# Connectors.net
KiCad netlist of a schematic drawn in Altium Designer
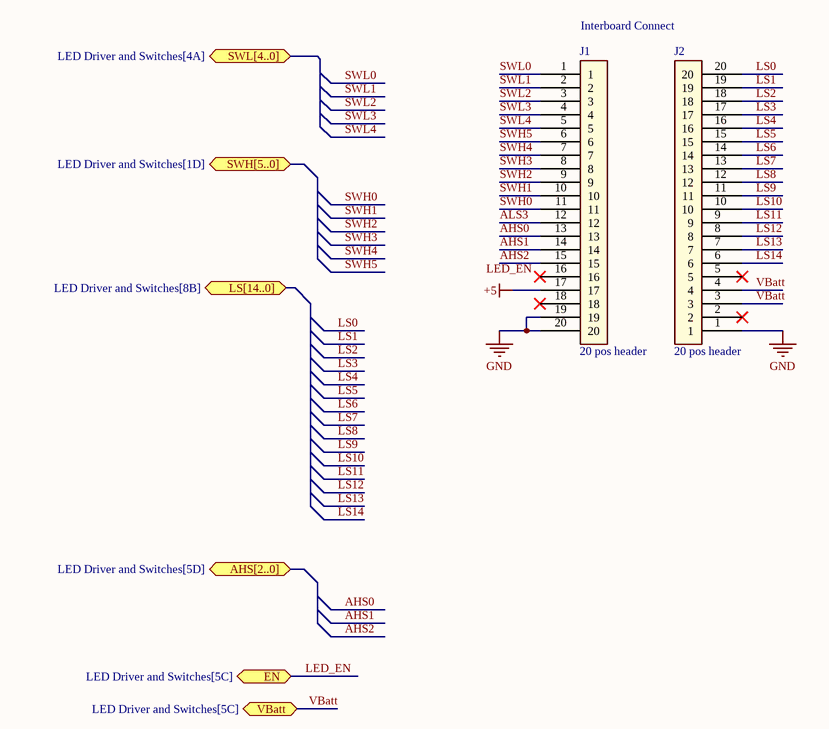
[diagram p0: Connectors.SchDoc]

(export (version "E")
  (design (tool "Eeschema 10.0.6"))
  (components
    (comp (ref "J1")
      (value "20 pos header")
      (footprint "20 pos header")
      (libsource (lib "2020-09-26_17-27-19") (part "20 pos header"))
    )
    (comp (ref "J2")
      (value "20 pos header")
      (footprint "20 pos header")
      (libsource (lib "") (part "20 pos header_1"))
    )
  )
  (nets
    (net (code "1") (name "+5") (class "Default")
      (node (ref "J1") (pin "17") (pinfunction "17_17") (pintype "passive"))
    )
    (net (code "2") (name "/AHS0") (class "Default")
      (node (ref "J1") (pin "13") (pinfunction "13_13") (pintype "passive"))
    )
    (net (code "3") (name "/AHS1") (class "Default")
      (node (ref "J1") (pin "14") (pinfunction "14_14") (pintype "passive"))
    )
    (net (code "4") (name "/AHS2") (class "Default")
      (node (ref "J1") (pin "15") (pinfunction "15_15") (pintype "passive"))
    )
    (net (code "6") (name "/ALS3") (class "Default")
      (node (ref "J1") (pin "12") (pinfunction "12_12") (pintype "passive"))
    )
    (net (code "8") (name "/LS0") (class "Default")
      (node (ref "J2") (pin "20") (pinfunction "20_20") (pintype "passive"))
    )
    (net (code "9") (name "/LS1") (class "Default")
      (node (ref "J2") (pin "19") (pinfunction "19_19") (pintype "passive"))
    )
    (net (code "10") (name "/LS2") (class "Default")
      (node (ref "J2") (pin "18") (pinfunction "18_18") (pintype "passive"))
    )
    (net (code "11") (name "/LS3") (class "Default")
      (node (ref "J2") (pin "17") (pinfunction "17_17") (pintype "passive"))
    )
    (net (code "12") (name "/LS4") (class "Default")
      (node (ref "J2") (pin "16") (pinfunction "16_16") (pintype "passive"))
    )
    (net (code "13") (name "/LS5") (class "Default")
      (node (ref "J2") (pin "15") (pinfunction "15_15") (pintype "passive"))
    )
    (net (code "14") (name "/LS6") (class "Default")
      (node (ref "J2") (pin "14") (pinfunction "14_14") (pintype "passive"))
    )
    (net (code "15") (name "/LS7") (class "Default")
      (node (ref "J2") (pin "13") (pinfunction "13_13") (pintype "passive"))
    )
    (net (code "16") (name "/LS8") (class "Default")
      (node (ref "J2") (pin "12") (pinfunction "12_12") (pintype "passive"))
    )
    (net (code "17") (name "/LS9") (class "Default")
      (node (ref "J2") (pin "11") (pinfunction "11_11") (pintype "passive"))
    )
    (net (code "18") (name "/LS10") (class "Default")
      (node (ref "J2") (pin "10") (pinfunction "10_10") (pintype "passive"))
    )
    (net (code "19") (name "/LS11") (class "Default")
      (node (ref "J2") (pin "9") (pinfunction "9_9") (pintype "passive"))
    )
    (net (code "20") (name "/LS12") (class "Default")
      (node (ref "J2") (pin "8") (pinfunction "8_8") (pintype "passive"))
    )
    (net (code "21") (name "/LS13") (class "Default")
      (node (ref "J2") (pin "7") (pinfunction "7_7") (pintype "passive"))
    )
    (net (code "22") (name "/LS14") (class "Default")
      (node (ref "J2") (pin "6") (pinfunction "6_6") (pintype "passive"))
    )
    (net (code "24") (name "/SWH0") (class "Default")
      (node (ref "J1") (pin "11") (pinfunction "11_11") (pintype "passive"))
    )
    (net (code "25") (name "/SWH1") (class "Default")
      (node (ref "J1") (pin "10") (pinfunction "10_10") (pintype "passive"))
    )
    (net (code "26") (name "/SWH2") (class "Default")
      (node (ref "J1") (pin "9") (pinfunction "9_9") (pintype "passive"))
    )
    (net (code "27") (name "/SWH3") (class "Default")
      (node (ref "J1") (pin "8") (pinfunction "8_8") (pintype "passive"))
    )
    (net (code "28") (name "/SWH4") (class "Default")
      (node (ref "J1") (pin "7") (pinfunction "7_7") (pintype "passive"))
    )
    (net (code "29") (name "/SWH5") (class "Default")
      (node (ref "J1") (pin "6") (pinfunction "6_6") (pintype "passive"))
    )
    (net (code "31") (name "/SWL0") (class "Default")
      (node (ref "J1") (pin "1") (pinfunction "1_1") (pintype "passive"))
    )
    (net (code "32") (name "/SWL1") (class "Default")
      (node (ref "J1") (pin "2") (pinfunction "2_2") (pintype "passive"))
    )
    (net (code "33") (name "/SWL2") (class "Default")
      (node (ref "J1") (pin "3") (pinfunction "3_3") (pintype "passive"))
    )
    (net (code "34") (name "/SWL3") (class "Default")
      (node (ref "J1") (pin "4") (pinfunction "4_4") (pintype "passive"))
    )
    (net (code "35") (name "/SWL4") (class "Default")
      (node (ref "J1") (pin "5") (pinfunction "5_5") (pintype "passive"))
    )
    (net (code "37") (name "/VBatt") (class "Default")
      (node (ref "J2") (pin "3") (pinfunction "3_3") (pintype "passive"))
      (node (ref "J2") (pin "4") (pinfunction "4_4") (pintype "passive"))
    )
    (net (code "38") (name "GND") (class "Default")
      (node (ref "J1") (pin "19") (pinfunction "19_19") (pintype "passive"))
      (node (ref "J1") (pin "20") (pinfunction "20_20") (pintype "passive"))
      (node (ref "J2") (pin "1") (pinfunction "1_1") (pintype "passive"))
    )
    (net (code "39") (name "unconnected-(J1-Pad16)") (class "Default")
      (node (ref "J1") (pin "16") (pinfunction "16_16") (pintype "passive+no_connect"))
    )
    (net (code "40") (name "unconnected-(J1-Pad18)") (class "Default")
      (node (ref "J1") (pin "18") (pinfunction "18_18") (pintype "passive+no_connect"))
    )
    (net (code "41") (name "unconnected-(J2-Pad2)") (class "Default")
      (node (ref "J2") (pin "2") (pinfunction "2_2") (pintype "passive+no_connect"))
    )
    (net (code "42") (name "unconnected-(J2-Pad5)") (class "Default")
      (node (ref "J2") (pin "5") (pinfunction "5_5") (pintype "passive+no_connect"))
    )
  )
)
